# fan.net
KiCad netlist of a schematic drawn in Altium Designer
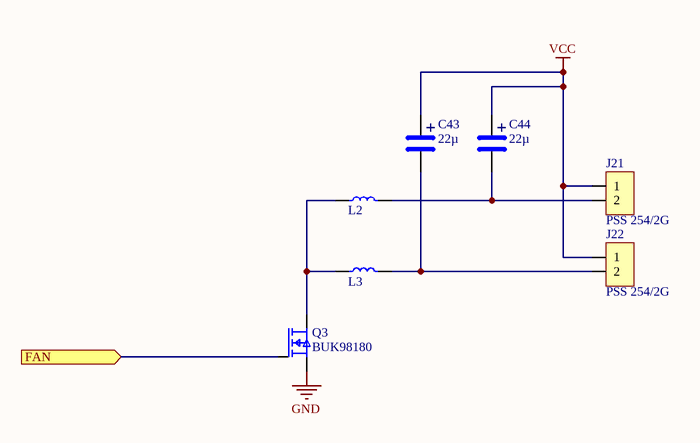
[diagram p0: fan.SchDoc]

(export (version "E")
  (design (tool "Eeschema 10.0.6"))
  (components
    (comp (ref "C43")
      (value "22µ")
      (footprint "WCAP-ASLU")
      (fields (field (name "VOLTAGE") "6.3V") (field (name "Comment") "Elko 22µF 6.3V WE"))
      (libsource (lib "elko") (part "Elko 22µF 6.3V WE"))
    )
    (comp (ref "C44")
      (value "22µ")
      (footprint "WCAP-ASLU")
      (fields (field (name "VOLTAGE") "6.3V") (field (name "Comment") "Elko 22µF 6.3V WE"))
      (libsource (lib "elko") (part "Elko 22µF 6.3V WE"))
    )
    (comp (ref "J21")
      (value "PSS 254/2G")
      (footprint "PSS 2pol")
      (description "PSS 2pol wire-to-board-connector")
      (libsource (lib "connectors_pss") (part "PSS 254/2G"))
    )
    (comp (ref "J22")
      (value "PSS 254/2G")
      (footprint "PSS 2pol")
      (description "PSS 2pol wire-to-board-connector")
      (libsource (lib "connectors_pss") (part "PSS 254/2G"))
    )
    (comp (ref "L2")
      (value "TDL_NL322522")
      (footprint "NL322522")
      (libsource (lib "inductors") (part "TDL_NL322522"))
    )
    (comp (ref "L3")
      (value "TDL_NL322522")
      (footprint "NL322522")
      (libsource (lib "inductors") (part "TDL_NL322522"))
    )
    (comp (ref "Q3")
      (value "BUK98180")
      (footprint "SOT223")
      (description "N-FET 100V 4.6A logic level")
      (libsource (lib "semiconductors") (part "BUK98180-100A"))
    )
  )
  (nets
    (net (code "1") (name "/FAN") (class "Default")
      (node (ref "Q3") (pin "1") (pinfunction "1_1") (pintype "passive"))
    )
    (net (code "2") (name "GND") (class "Default")
      (node (ref "Q3") (pin "3") (pinfunction "3_3") (pintype "passive"))
    )
    (net (code "3") (name "Net-(C43-Pad-)") (class "Default")
      (node (ref "C43") (pin "-") (pinfunction "-_-") (pintype "passive"))
      (node (ref "J22") (pin "2") (pinfunction "2_2") (pintype "passive"))
      (node (ref "L3") (pin "2") (pinfunction "2_2") (pintype "passive"))
    )
    (net (code "4") (name "Net-(C44-Pad-)") (class "Default")
      (node (ref "C44") (pin "-") (pinfunction "-_-") (pintype "passive"))
      (node (ref "J21") (pin "2") (pinfunction "2_2") (pintype "passive"))
      (node (ref "L2") (pin "2") (pinfunction "2_2") (pintype "passive"))
    )
    (net (code "5") (name "Net-(L2-Pad1)") (class "Default")
      (node (ref "L2") (pin "1") (pinfunction "1_1") (pintype "passive"))
      (node (ref "L3") (pin "1") (pinfunction "1_1") (pintype "passive"))
      (node (ref "Q3") (pin "2") (pinfunction "2_2") (pintype "passive"))
    )
    (net (code "6") (name "VCC") (class "Default")
      (node (ref "C43") (pin "+") (pinfunction "+_+") (pintype "passive"))
      (node (ref "C44") (pin "+") (pinfunction "+_+") (pintype "passive"))
      (node (ref "J21") (pin "1") (pinfunction "1_1") (pintype "passive"))
      (node (ref "J22") (pin "1") (pinfunction "1_1") (pintype "passive"))
    )
  )
)
